# jefboard1_1.net
KiCad netlist of a schematic drawn in EAGLE
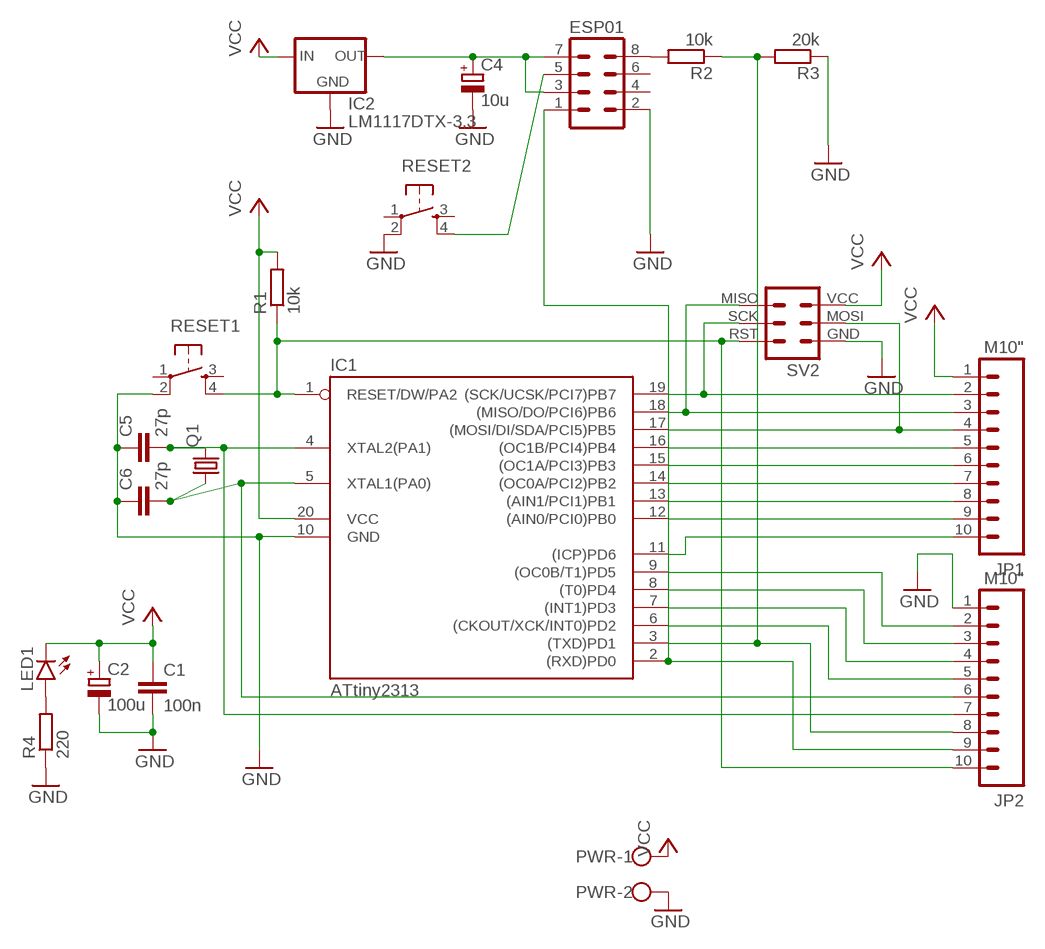
[diagram p0: schematic, sheet 1]

(export (version "E")
  (design (tool "Eeschema 10.0.6"))
  (components
    (comp (ref "C1")
      (value "100n")
      (footprint "eagle-import:C025-025X050")
      (libsource (lib "eagle-import") (part "C-EU025-025X050"))
    )
    (comp (ref "C2")
      (value "100u")
      (footprint "eagle-import:E2,5-5")
      (libsource (lib "eagle-import") (part "CPOL-EUE2.5-5"))
    )
    (comp (ref "C4")
      (value "10u")
      (footprint "eagle-import:E2,5-5")
      (libsource (lib "eagle-import") (part "CPOL-EUE2.5-5"))
    )
    (comp (ref "C5")
      (value "27p")
      (footprint "eagle-import:C2.5-2")
      (libsource (lib "eagle-import") (part "C2.5/2"))
    )
    (comp (ref "C6")
      (value "27p")
      (footprint "eagle-import:C2.5-2")
      (libsource (lib "eagle-import") (part "C2.5/2"))
    )
    (comp (ref "ESP01")
      (value "MA04-2")
      (footprint "eagle-import:MA04-2")
      (libsource (lib "eagle-import") (part "MA04-2"))
    )
    (comp (ref "IC1")
      (value "ATtiny2313")
      (footprint "eagle-import:DIL20")
      (libsource (lib "eagle-import") (part "ATTINY2313P-20"))
    )
    (comp (ref "IC2")
      (value "LM1117DTX-3.3")
      (footprint "eagle-import:TO252")
      (libsource (lib "eagle-import") (part "LM1117DTX-3.3"))
    )
    (comp (ref "JP1")
      (value "M10\"")
      (footprint "eagle-import:1X10")
      (libsource (lib "eagle-import") (part "M10{dblquote}"))
    )
    (comp (ref "JP2")
      (value "M10\"")
      (footprint "eagle-import:1X10")
      (libsource (lib "eagle-import") (part "M10{dblquote}"))
    )
    (comp (ref "LED1")
      (value "LED3MM")
      (footprint "eagle-import:LED3MM")
      (libsource (lib "eagle-import") (part "LED3MM"))
    )
    (comp (ref "PWR")
      (value "W237-102")
      (footprint "eagle-import:W237-102")
      (fields (field (name "MPN") "237-102"))
      (libsource (lib "eagle-import") (part "W237-102"))
    )
    (comp (ref "Q1")
      (value "CRYSTALHC49S")
      (footprint "eagle-import:HC49_S")
      (libsource (lib "eagle-import") (part "CRYSTALHC49S"))
    )
    (comp (ref "R1")
      (value "10k")
      (footprint "eagle-import:0207_5V")
      (libsource (lib "eagle-import") (part "R-EU_0207/5V"))
    )
    (comp (ref "R2")
      (value "10k")
      (footprint "eagle-import:0207_5V")
      (libsource (lib "eagle-import") (part "R-EU_0207/5V"))
    )
    (comp (ref "R3")
      (value "20k")
      (footprint "eagle-import:0207_5V")
      (libsource (lib "eagle-import") (part "R-EU_0207/5V"))
    )
    (comp (ref "R4")
      (value "220")
      (footprint "eagle-import:0207_5V")
      (libsource (lib "eagle-import") (part "R-EU_0207/5V"))
    )
    (comp (ref "RESET1")
      (value "TAC_SWITCHPTH")
      (footprint "eagle-import:TACTILE-PTH")
      (libsource (lib "eagle-import") (part "TAC_SWITCHPTH"))
    )
    (comp (ref "RESET2")
      (value "TAC_SWITCHPTH")
      (footprint "eagle-import:TACTILE-PTH")
      (libsource (lib "eagle-import") (part "TAC_SWITCHPTH"))
    )
    (comp (ref "SV2")
      (value "MA03-2")
      (footprint "eagle-import:MA03-2")
      (libsource (lib "eagle-import") (part "MA03-2"))
    )
  )
  (nets
    (net (code "1") (name "GND") (class "Default")
      (node (ref "C1") (pin "2") (pinfunction "2_2") (pintype "passive"))
      (node (ref "C2") (pin "-") (pinfunction "-_-") (pintype "passive"))
      (node (ref "C4") (pin "-") (pinfunction "-_-") (pintype "passive"))
      (node (ref "C5") (pin "1") (pinfunction "1_1") (pintype "passive"))
      (node (ref "C6") (pin "1") (pinfunction "1_1") (pintype "passive"))
      (node (ref "ESP01") (pin "2") (pinfunction "2_2") (pintype "passive"))
      (node (ref "IC1") (pin "10") (pinfunction "GND_10") (pintype "power_in"))
      (node (ref "IC2") (pin "1") (pinfunction "GND_1") (pintype "input"))
      (node (ref "JP2") (pin "1") (pinfunction "1_1") (pintype "passive"))
      (node (ref "PWR") (pin "2") (pinfunction "KL_2") (pintype "passive"))
      (node (ref "R3") (pin "1") (pinfunction "1_1") (pintype "passive"))
      (node (ref "R4") (pin "1") (pinfunction "1_1") (pintype "passive"))
      (node (ref "RESET1") (pin "2") (pinfunction "2_2") (pintype "passive"))
      (node (ref "RESET2") (pin "2") (pinfunction "2_2") (pintype "passive"))
      (node (ref "SV2") (pin "GND") (pinfunction "GND_GND") (pintype "passive"))
    )
    (net (code "2") (name "Net-(ESP01-Pad5)") (class "Default")
      (node (ref "ESP01") (pin "5") (pinfunction "5_5") (pintype "passive"))
      (node (ref "RESET2") (pin "4") (pinfunction "4_4") (pintype "passive"))
    )
    (net (code "3") (name "Net-(ESP01-Pad8)") (class "Default")
      (node (ref "ESP01") (pin "8") (pinfunction "8_8") (pintype "passive"))
      (node (ref "R2") (pin "2") (pinfunction "2_2") (pintype "passive"))
    )
    (net (code "4") (name "Net-(IC1-(AIN0{slash}PCI0)PB0)") (class "Default")
      (node (ref "IC1") (pin "12") (pinfunction "(AIN0/PCI0)PB0_12") (pintype "bidirectional"))
      (node (ref "JP1") (pin "9") (pinfunction "9_9") (pintype "passive"))
    )
    (net (code "5") (name "Net-(IC1-(AIN1{slash}PCI1)PB1)") (class "Default")
      (node (ref "IC1") (pin "13") (pinfunction "(AIN1/PCI1)PB1_13") (pintype "bidirectional"))
      (node (ref "JP1") (pin "8") (pinfunction "8_8") (pintype "passive"))
    )
    (net (code "6") (name "Net-(IC1-(CKOUT{slash}XCK{slash}INT0)PD2)") (class "Default")
      (node (ref "IC1") (pin "6") (pinfunction "(CKOUT/XCK/INT0)PD2_6") (pintype "bidirectional"))
      (node (ref "JP2") (pin "5") (pinfunction "5_5") (pintype "passive"))
    )
    (net (code "7") (name "Net-(IC1-(ICP)PD6)") (class "Default")
      (node (ref "IC1") (pin "11") (pinfunction "(ICP)PD6_11") (pintype "bidirectional"))
      (node (ref "JP1") (pin "10") (pinfunction "10_10") (pintype "passive"))
    )
    (net (code "8") (name "Net-(IC1-(INT1)PD3)") (class "Default")
      (node (ref "IC1") (pin "7") (pinfunction "(INT1)PD3_7") (pintype "bidirectional"))
      (node (ref "JP2") (pin "4") (pinfunction "4_4") (pintype "passive"))
    )
    (net (code "9") (name "Net-(IC1-(MISO{slash}DO{slash}PCI6)PB6)") (class "Default")
      (node (ref "IC1") (pin "18") (pinfunction "(MISO/DO/PCI6)PB6_18") (pintype "bidirectional"))
      (node (ref "JP1") (pin "3") (pinfunction "3_3") (pintype "passive"))
      (node (ref "SV2") (pin "MISO") (pinfunction "MISO_MISO") (pintype "passive"))
    )
    (net (code "10") (name "Net-(IC1-(MOSI{slash}DI{slash}SDA{slash}PCI5)PB5)") (class "Default")
      (node (ref "IC1") (pin "17") (pinfunction "(MOSI/DI/SDA/PCI5)PB5_17") (pintype "bidirectional"))
      (node (ref "JP1") (pin "4") (pinfunction "4_4") (pintype "passive"))
      (node (ref "SV2") (pin "MOSI") (pinfunction "MOSI_MOSI") (pintype "passive"))
    )
    (net (code "11") (name "Net-(IC1-(OC0A{slash}PCI2)PB2)") (class "Default")
      (node (ref "IC1") (pin "14") (pinfunction "(OC0A/PCI2)PB2_14") (pintype "bidirectional"))
      (node (ref "JP1") (pin "7") (pinfunction "7_7") (pintype "passive"))
    )
    (net (code "12") (name "Net-(IC1-(OC0B{slash}T1)PD5)") (class "Default")
      (node (ref "IC1") (pin "9") (pinfunction "(OC0B/T1)PD5_9") (pintype "bidirectional"))
      (node (ref "JP2") (pin "2") (pinfunction "2_2") (pintype "passive"))
    )
    (net (code "13") (name "Net-(IC1-(OC1A{slash}PCI3)PB3)") (class "Default")
      (node (ref "IC1") (pin "15") (pinfunction "(OC1A/PCI3)PB3_15") (pintype "bidirectional"))
      (node (ref "JP1") (pin "6") (pinfunction "6_6") (pintype "passive"))
    )
    (net (code "14") (name "Net-(IC1-(OC1B{slash}PCI4)PB4)") (class "Default")
      (node (ref "IC1") (pin "16") (pinfunction "(OC1B/PCI4)PB4_16") (pintype "bidirectional"))
      (node (ref "JP1") (pin "5") (pinfunction "5_5") (pintype "passive"))
    )
    (net (code "15") (name "Net-(IC1-(RXD)PD0)") (class "Default")
      (node (ref "ESP01") (pin "1") (pinfunction "1_1") (pintype "passive"))
      (node (ref "IC1") (pin "2") (pinfunction "(RXD)PD0_2") (pintype "bidirectional"))
      (node (ref "JP2") (pin "9") (pinfunction "9_9") (pintype "passive"))
    )
    (net (code "16") (name "Net-(IC1-(SCK{slash}UCSK{slash}PCI7)PB7)") (class "Default")
      (node (ref "IC1") (pin "19") (pinfunction "(SCK/UCSK/PCI7)PB7_19") (pintype "bidirectional"))
      (node (ref "JP1") (pin "2") (pinfunction "2_2") (pintype "passive"))
      (node (ref "SV2") (pin "SCK") (pinfunction "SCK_SCK") (pintype "passive"))
    )
    (net (code "17") (name "Net-(IC1-(T0)PD4)") (class "Default")
      (node (ref "IC1") (pin "8") (pinfunction "(T0)PD4_8") (pintype "bidirectional"))
      (node (ref "JP2") (pin "3") (pinfunction "3_3") (pintype "passive"))
    )
    (net (code "18") (name "Net-(IC1-(TXD)PD1)") (class "Default")
      (node (ref "IC1") (pin "3") (pinfunction "(TXD)PD1_3") (pintype "bidirectional"))
      (node (ref "JP2") (pin "8") (pinfunction "8_8") (pintype "passive"))
      (node (ref "R2") (pin "1") (pinfunction "1_1") (pintype "passive"))
      (node (ref "R3") (pin "2") (pinfunction "2_2") (pintype "passive"))
    )
    (net (code "19") (name "Net-(IC1-RESET{slash}DW{slash}PA2)") (class "Default")
      (node (ref "IC1") (pin "1") (pinfunction "RESET/DW/PA2_1") (pintype "bidirectional"))
      (node (ref "JP2") (pin "10") (pinfunction "10_10") (pintype "passive"))
      (node (ref "R1") (pin "1") (pinfunction "1_1") (pintype "passive"))
      (node (ref "RESET1") (pin "4") (pinfunction "4_4") (pintype "passive"))
      (node (ref "SV2") (pin "RST") (pinfunction "RST_RST") (pintype "passive"))
    )
    (net (code "20") (name "Net-(IC1-XTAL1(PA0))") (class "Default")
      (node (ref "C6") (pin "2") (pinfunction "2_2") (pintype "passive"))
      (node (ref "IC1") (pin "5") (pinfunction "XTAL1(PA0)_5") (pintype "bidirectional"))
      (node (ref "JP2") (pin "6") (pinfunction "6_6") (pintype "passive"))
      (node (ref "Q1") (pin "1") (pinfunction "1_1") (pintype "passive"))
    )
    (net (code "21") (name "Net-(IC1-XTAL2(PA1))") (class "Default")
      (node (ref "C5") (pin "2") (pinfunction "2_2") (pintype "passive"))
      (node (ref "IC1") (pin "4") (pinfunction "XTAL2(PA1)_4") (pintype "bidirectional"))
      (node (ref "JP2") (pin "7") (pinfunction "7_7") (pintype "passive"))
      (node (ref "Q1") (pin "2") (pinfunction "2_2") (pintype "passive"))
    )
    (net (code "22") (name "Net-(IC2-OUT)") (class "Default")
      (node (ref "C4") (pin "+") (pinfunction "+_+") (pintype "passive"))
      (node (ref "ESP01") (pin "3") (pinfunction "3_3") (pintype "passive"))
      (node (ref "ESP01") (pin "7") (pinfunction "7_7") (pintype "passive"))
      (node (ref "IC2") (pin "TAB") (pinfunction "OUT_TAB") (pintype "passive"))
    )
    (net (code "23") (name "Net-(LED1-PadA)") (class "Default")
      (node (ref "LED1") (pin "A") (pinfunction "A_A") (pintype "passive"))
      (node (ref "R4") (pin "2") (pinfunction "2_2") (pintype "passive"))
    )
    (net (code "24") (name "VCC") (class "Default")
      (node (ref "C1") (pin "1") (pinfunction "1_1") (pintype "passive"))
      (node (ref "C2") (pin "+") (pinfunction "+_+") (pintype "passive"))
      (node (ref "IC1") (pin "20") (pinfunction "VCC_20") (pintype "power_in"))
      (node (ref "IC2") (pin "2") (pinfunction "IN_2") (pintype "input"))
      (node (ref "JP1") (pin "1") (pinfunction "1_1") (pintype "passive"))
      (node (ref "LED1") (pin "K") (pinfunction "C_K") (pintype "passive"))
      (node (ref "PWR") (pin "1") (pinfunction "KL_1") (pintype "passive"))
      (node (ref "R1") (pin "2") (pinfunction "2_2") (pintype "passive"))
      (node (ref "SV2") (pin "VCC") (pinfunction "VCC_VCC") (pintype "passive"))
    )
    (net (code "25") (name "unconnected-(ESP01-Pad4)") (class "Default")
      (node (ref "ESP01") (pin "4") (pinfunction "4_4") (pintype "passive"))
    )
    (net (code "26") (name "unconnected-(ESP01-Pad6)") (class "Default")
      (node (ref "ESP01") (pin "6") (pinfunction "6_6") (pintype "passive"))
    )
    (net (code "27") (name "unconnected-(RESET1-Pad1)") (class "Default")
      (node (ref "RESET1") (pin "1") (pinfunction "1_1") (pintype "passive"))
    )
    (net (code "28") (name "unconnected-(RESET1-Pad3)") (class "Default")
      (node (ref "RESET1") (pin "3") (pinfunction "3_3") (pintype "passive"))
    )
    (net (code "29") (name "unconnected-(RESET2-Pad1)") (class "Default")
      (node (ref "RESET2") (pin "1") (pinfunction "1_1") (pintype "passive"))
    )
    (net (code "30") (name "unconnected-(RESET2-Pad3)") (class "Default")
      (node (ref "RESET2") (pin "3") (pinfunction "3_3") (pintype "passive"))
    )
  )
)
